# blink1_v2d.net
KiCad netlist of a schematic drawn in EAGLE
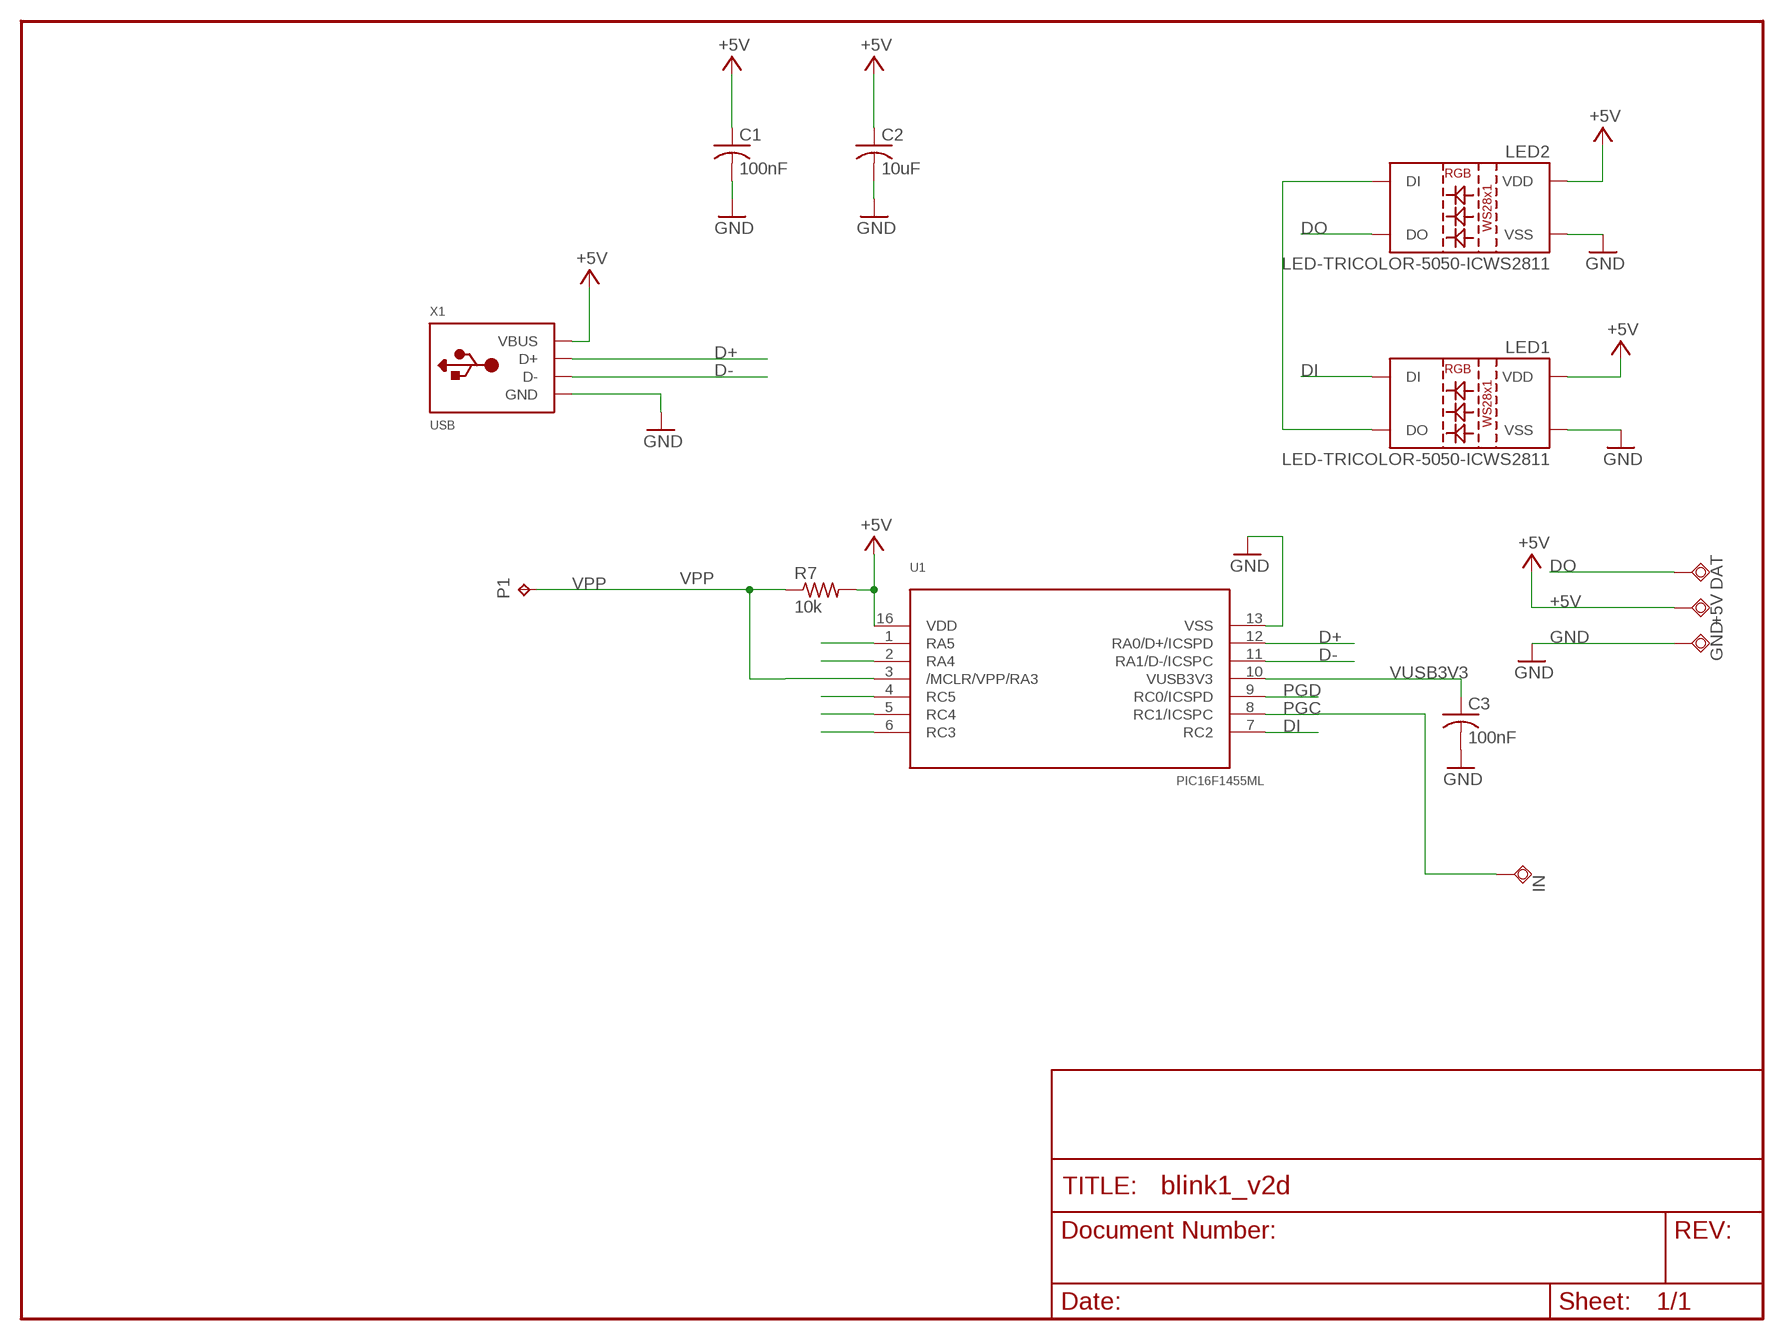
[diagram p0: schematic, sheet 1]

(export (version "E")
  (design (tool "Eeschema 10.0.6"))
  (components
    (comp (ref "+5V")
      (value "TPSQTP12SQ")
      (footprint "eagle-import:TP12SQ")
      (libsource (lib "eagle-import") (part "TPSQTP12SQ"))
    )
    (comp (ref "C1")
      (value "100nF")
      (footprint "eagle-import:C0603")
      (libsource (lib "eagle-import") (part "C-USC0603"))
    )
    (comp (ref "C2")
      (value "10uF")
      (footprint "eagle-import:C0603")
      (libsource (lib "eagle-import") (part "C-USC0603"))
    )
    (comp (ref "C3")
      (value "100nF")
      (footprint "eagle-import:C0603")
      (libsource (lib "eagle-import") (part "C-USC0603"))
    )
    (comp (ref "DAT")
      (value "TPSQTP12SQ")
      (footprint "eagle-import:TP12SQ")
      (libsource (lib "eagle-import") (part "TPSQTP12SQ"))
    )
    (comp (ref "GND")
      (value "TPSQTP12SQ")
      (footprint "eagle-import:TP12SQ")
      (libsource (lib "eagle-import") (part "TPSQTP12SQ"))
    )
    (comp (ref "IN")
      (value "TPSQTP12SQ")
      (footprint "eagle-import:TP12SQ")
      (libsource (lib "eagle-import") (part "TPSQTP12SQ"))
    )
    (comp (ref "LED1")
      (value "LED-TRICOLOR-5050-ICWS2811")
      (footprint "eagle-import:LED-TRICOLOR-5050-IC")
      (libsource (lib "eagle-import") (part "LED-TRICOLOR-5050-ICWS2811"))
    )
    (comp (ref "LED2")
      (value "LED-TRICOLOR-5050-ICWS2811")
      (footprint "eagle-import:LED-TRICOLOR-5050-IC")
      (libsource (lib "eagle-import") (part "LED-TRICOLOR-5050-ICWS2811"))
    )
    (comp (ref "P1")
      (value "TPTP11SQ")
      (footprint "eagle-import:TP11SQ")
      (libsource (lib "eagle-import") (part "TPTP11SQ"))
    )
    (comp (ref "R7")
      (value "10k")
      (footprint "eagle-import:R0603")
      (libsource (lib "eagle-import") (part "R-US_R0603"))
    )
    (comp (ref "U1")
      (value "PIC16F1455ML")
      (footprint "eagle-import:QFN16_4X4")
      (libsource (lib "eagle-import") (part "PIC16F1455ML"))
    )
    (comp (ref "X1")
      (value "USB")
      (footprint "eagle-import:MOLEX-48037-1000")
      (libsource (lib "eagle-import") (part "USB"))
    )
  )
  (nets
    (net (code "1") (name "+5V") (class "Default")
      (node (ref "+5V") (pin "TP") (pinfunction "TP_TP") (pintype "input"))
      (node (ref "C1") (pin "1") (pinfunction "1_1") (pintype "passive"))
      (node (ref "C2") (pin "1") (pinfunction "1_1") (pintype "passive"))
      (node (ref "LED1") (pin "3") (pinfunction "VDD_3") (pintype "bidirectional"))
      (node (ref "LED1") (pin "5") (pinfunction "VDD_5") (pintype "bidirectional"))
      (node (ref "LED2") (pin "3") (pinfunction "VDD_3") (pintype "bidirectional"))
      (node (ref "LED2") (pin "5") (pinfunction "VDD_5") (pintype "bidirectional"))
      (node (ref "R7") (pin "2") (pinfunction "2_2") (pintype "passive"))
      (node (ref "U1") (pin "16") (pinfunction "VDD_16") (pintype "bidirectional"))
      (node (ref "X1") (pin "1") (pinfunction "VBUS_1") (pintype "power_in"))
    )
    (net (code "2") (name "/D+") (class "Default")
      (node (ref "U1") (pin "12") (pinfunction "RA0/D+/ICSPD_12") (pintype "bidirectional"))
      (node (ref "X1") (pin "3") (pinfunction "D+_3") (pintype "bidirectional"))
    )
    (net (code "3") (name "/D-") (class "Default")
      (node (ref "U1") (pin "11") (pinfunction "RA1/D-/ICSPC_11") (pintype "bidirectional"))
      (node (ref "X1") (pin "2") (pinfunction "D-_2") (pintype "bidirectional"))
    )
    (net (code "4") (name "/DI") (class "Default")
      (node (ref "LED1") (pin "2") (pinfunction "DI_2") (pintype "bidirectional"))
      (node (ref "U1") (pin "7") (pinfunction "RC2_7") (pintype "bidirectional"))
    )
    (net (code "5") (name "/DO") (class "Default")
      (node (ref "DAT") (pin "TP") (pinfunction "TP_TP") (pintype "input"))
      (node (ref "LED2") (pin "1") (pinfunction "DO_1") (pintype "bidirectional"))
    )
    (net (code "6") (name "/PGC") (class "Default")
      (node (ref "IN") (pin "TP") (pinfunction "TP_TP") (pintype "input"))
      (node (ref "U1") (pin "8") (pinfunction "RC1/ICSPC_8") (pintype "bidirectional"))
    )
    (net (code "7") (name "/PGD") (class "Default")
      (node (ref "U1") (pin "9") (pinfunction "RC0/ICSPD_9") (pintype "bidirectional"))
    )
    (net (code "8") (name "/VPP") (class "Default")
      (node (ref "P1") (pin "TP") (pinfunction "TP_TP") (pintype "input"))
      (node (ref "R7") (pin "1") (pinfunction "1_1") (pintype "passive"))
      (node (ref "U1") (pin "3") (pinfunction "/MCLR/VPP/RA3_3") (pintype "bidirectional"))
    )
    (net (code "9") (name "/VUSB3V3") (class "Default")
      (node (ref "C3") (pin "1") (pinfunction "1_1") (pintype "passive"))
      (node (ref "U1") (pin "10") (pinfunction "VUSB3V3_10") (pintype "bidirectional"))
    )
    (net (code "10") (name "GND") (class "Default")
      (node (ref "C1") (pin "2") (pinfunction "2_2") (pintype "passive"))
      (node (ref "C2") (pin "2") (pinfunction "2_2") (pintype "passive"))
      (node (ref "C3") (pin "2") (pinfunction "2_2") (pintype "passive"))
      (node (ref "GND") (pin "TP") (pinfunction "TP_TP") (pintype "input"))
      (node (ref "LED1") (pin "6") (pinfunction "VSS_6") (pintype "bidirectional"))
      (node (ref "LED2") (pin "6") (pinfunction "VSS_6") (pintype "bidirectional"))
      (node (ref "U1") (pin "13") (pinfunction "VSS_13") (pintype "bidirectional"))
      (node (ref "X1") (pin "4") (pinfunction "GND_4") (pintype "power_in"))
    )
    (net (code "11") (name "Net-(LED1-DO)") (class "Default")
      (node (ref "LED1") (pin "1") (pinfunction "DO_1") (pintype "bidirectional"))
      (node (ref "LED2") (pin "2") (pinfunction "DI_2") (pintype "bidirectional"))
    )
    (net (code "12") (name "unconnected-(U1-RA4-Pad2)") (class "Default")
      (node (ref "U1") (pin "2") (pinfunction "RA4_2") (pintype "bidirectional"))
    )
    (net (code "13") (name "unconnected-(U1-RA5-Pad1)") (class "Default")
      (node (ref "U1") (pin "1") (pinfunction "RA5_1") (pintype "bidirectional"))
    )
    (net (code "14") (name "unconnected-(U1-RC3-Pad6)") (class "Default")
      (node (ref "U1") (pin "6") (pinfunction "RC3_6") (pintype "bidirectional"))
    )
    (net (code "15") (name "unconnected-(U1-RC4-Pad5)") (class "Default")
      (node (ref "U1") (pin "5") (pinfunction "RC4_5") (pintype "bidirectional"))
    )
    (net (code "16") (name "unconnected-(U1-RC5-Pad4)") (class "Default")
      (node (ref "U1") (pin "4") (pinfunction "RC5_4") (pintype "bidirectional"))
    )
  )
)
